# SubClockFix.net
KiCad netlist of a schematic drawn in EAGLE
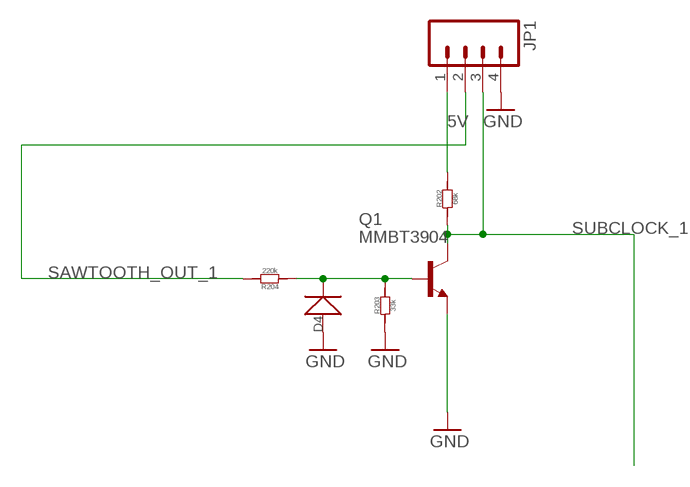
[diagram p0: schematic, sheet 1]

(export (version "E")
  (design (tool "Eeschema 10.0.6"))
  (components
    (comp (ref "D4")
      (value "D-SMA")
      (footprint "eagle-import:DO-214AC")
      (libsource (lib "eagle-import") (part "D-SMA"))
    )
    (comp (ref "JP1")
      (value "M04PTH")
      (footprint "eagle-import:1X04")
      (libsource (lib "eagle-import") (part "M04PTH"))
    )
    (comp (ref "Q1")
      (value "MMBT3904")
      (footprint "eagle-import:SOT23-BEC")
      (fields (field (name "MF") "NXP") (field (name "MPN") "PMBT3904,215"))
      (libsource (lib "eagle-import") (part "-NPN-SOT23-BECMMBT3904LT1"))
    )
    (comp (ref "R202")
      (value "68k")
      (footprint "eagle-import:R0603")
      (libsource (lib "eagle-import") (part "R-0603"))
    )
    (comp (ref "R203")
      (value "33k")
      (footprint "eagle-import:R0603")
      (libsource (lib "eagle-import") (part "R-0603"))
    )
    (comp (ref "R204")
      (value "220k")
      (footprint "eagle-import:R0603")
      (libsource (lib "eagle-import") (part "R-0603"))
    )
  )
  (nets
    (net (code "1") (name "/5V") (class "Default")
      (node (ref "JP1") (pin "1") (pinfunction "1_1") (pintype "passive"))
      (node (ref "R202") (pin "2") (pinfunction "2_2") (pintype "bidirectional"))
    )
    (net (code "2") (name "/SAWTOOTH_OUT_1") (class "Default")
      (node (ref "JP1") (pin "2") (pinfunction "2_2") (pintype "passive"))
      (node (ref "R204") (pin "2") (pinfunction "2_2") (pintype "bidirectional"))
    )
    (net (code "3") (name "/SUBCLOCK_1") (class "Default")
      (node (ref "JP1") (pin "3") (pinfunction "3_3") (pintype "passive"))
      (node (ref "Q1") (pin "C") (pinfunction "C_C") (pintype "passive"))
      (node (ref "R202") (pin "1") (pinfunction "1_1") (pintype "bidirectional"))
    )
    (net (code "4") (name "GND") (class "Default")
      (node (ref "D4") (pin "1") (pinfunction "+_1") (pintype "passive"))
      (node (ref "JP1") (pin "4") (pinfunction "4_4") (pintype "passive"))
      (node (ref "Q1") (pin "E") (pinfunction "E_E") (pintype "passive"))
      (node (ref "R203") (pin "1") (pinfunction "1_1") (pintype "bidirectional"))
    )
    (net (code "5") (name "Net-(D4--)") (class "Default")
      (node (ref "D4") (pin "2") (pinfunction "-_2") (pintype "passive"))
      (node (ref "Q1") (pin "B") (pinfunction "B_B") (pintype "passive"))
      (node (ref "R203") (pin "2") (pinfunction "2_2") (pintype "bidirectional"))
      (node (ref "R204") (pin "1") (pinfunction "1_1") (pintype "bidirectional"))
    )
  )
)
